# espThrottle.net
KiCad netlist of a schematic drawn in EAGLE
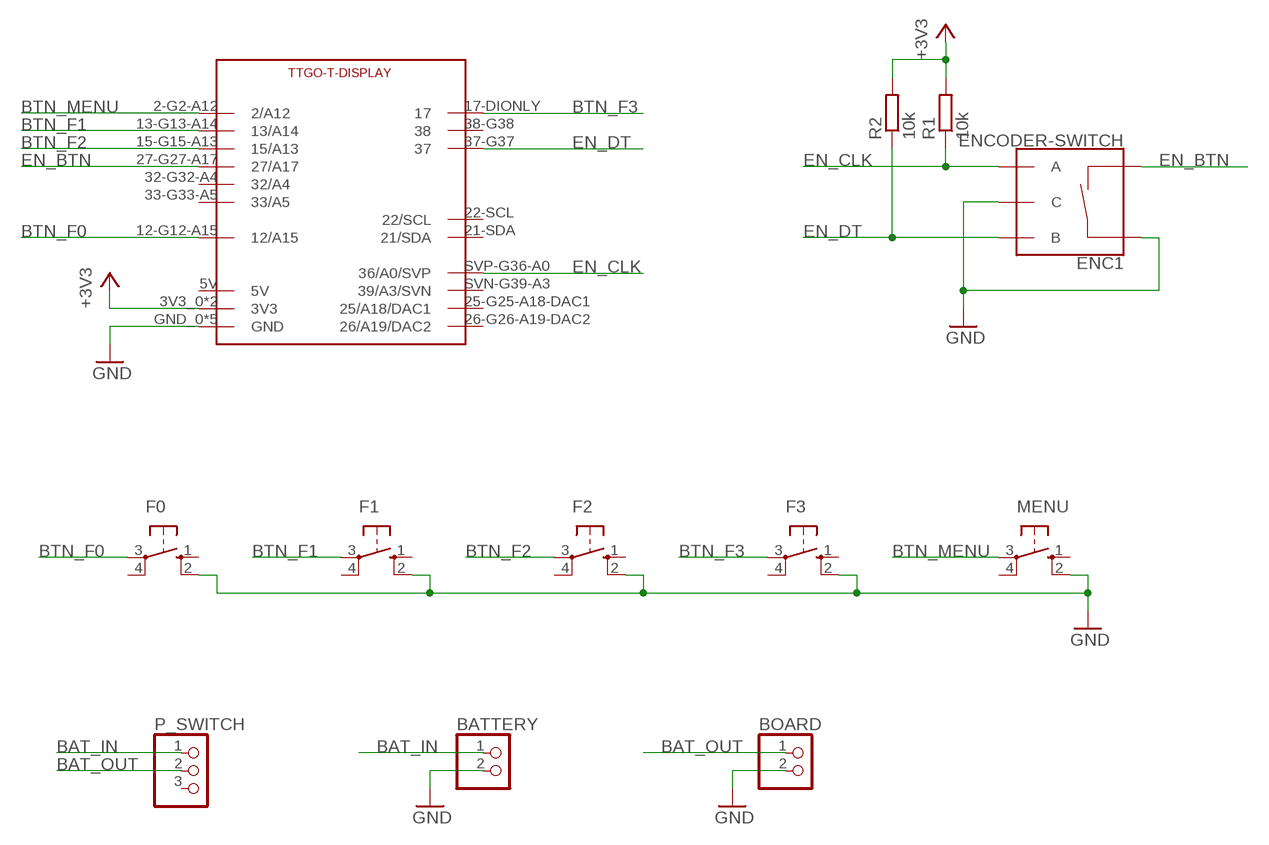
[diagram p0: schematic, sheet 1]

(export (version "E")
  (design (tool "Eeschema 10.0.6"))
  (components
    (comp (ref "BATTERY")
      (value "PINHD-1X2")
      (footprint "eagle-import:1X02")
      (libsource (lib "eagle-import") (part "PINHD-1X2"))
    )
    (comp (ref "BOARD")
      (value "PINHD-1X2")
      (footprint "eagle-import:1X02")
      (libsource (lib "eagle-import") (part "PINHD-1X2"))
    )
    (comp (ref "ENC1")
      (value "ENCODER-SWITCH")
      (footprint "eagle-import:ROTARY_ENC_PLAIN")
      (libsource (lib "eagle-import") (part "ENCODER-SWITCH"))
    )
    (comp (ref "F0")
      (value "10-XX")
      (footprint "eagle-import:B3F-10XX")
      (fields (field (name "MPN") "B3F-1000"))
      (libsource (lib "eagle-import") (part "10-XX"))
    )
    (comp (ref "F1")
      (value "10-XX")
      (footprint "eagle-import:B3F-10XX")
      (fields (field (name "MPN") "B3F-1000"))
      (libsource (lib "eagle-import") (part "10-XX"))
    )
    (comp (ref "F2")
      (value "10-XX")
      (footprint "eagle-import:B3F-10XX")
      (fields (field (name "MPN") "B3F-1000"))
      (libsource (lib "eagle-import") (part "10-XX"))
    )
    (comp (ref "F3")
      (value "10-XX")
      (footprint "eagle-import:B3F-10XX")
      (fields (field (name "MPN") "B3F-1000"))
      (libsource (lib "eagle-import") (part "10-XX"))
    )
    (comp (ref "MENU")
      (value "10-XX")
      (footprint "eagle-import:B3F-10XX")
      (fields (field (name "MPN") "B3F-1000"))
      (libsource (lib "eagle-import") (part "10-XX"))
    )
    (comp (ref "P_SWITCH")
      (value "PINHD-1X3")
      (footprint "eagle-import:1X03")
      (libsource (lib "eagle-import") (part "PINHD-1X3"))
    )
    (comp (ref "R1")
      (value "10k")
      (footprint "eagle-import:0207_12")
      (libsource (lib "eagle-import") (part "R-EU_0207/12"))
    )
    (comp (ref "R2")
      (value "10k")
      (footprint "eagle-import:0207_12")
      (libsource (lib "eagle-import") (part "R-EU_0207/12"))
    )
    (comp (ref "U$1")
      (value "TTGO-T-DISPLAYFRAME")
      (footprint "eagle-import:TTGO-T-DISPLAY-OL")
      (libsource (lib "eagle-import") (part "TTGO-T-DISPLAYFRAME"))
    )
  )
  (nets
    (net (code "1") (name "+3V3") (class "Default")
      (node (ref "R1") (pin "2") (pinfunction "2_2") (pintype "passive"))
      (node (ref "R2") (pin "2") (pinfunction "2_2") (pintype "passive"))
      (node (ref "U$1") (pin "3V3_0") (pinfunction "3V3_3V3_0") (pintype "power_in"))
      (node (ref "U$1") (pin "3V3_1") (pinfunction "3V3_3V3_1") (pintype "power_in"))
    )
    (net (code "2") (name "/5V") (class "Default")
      (node (ref "U$1") (pin "5V") (pinfunction "5V_5V") (pintype "power_in"))
    )
    (net (code "3") (name "/BAT_IN") (class "Default")
      (node (ref "BATTERY") (pin "1") (pinfunction "1_1") (pintype "passive"))
      (node (ref "P_SWITCH") (pin "1") (pinfunction "1_1") (pintype "passive"))
    )
    (net (code "4") (name "/BAT_OUT") (class "Default")
      (node (ref "BOARD") (pin "1") (pinfunction "1_1") (pintype "passive"))
      (node (ref "P_SWITCH") (pin "2") (pinfunction "2_2") (pintype "passive"))
    )
    (net (code "5") (name "/BTN_F0") (class "Default")
      (node (ref "F0") (pin "3") (pinfunction "P_3") (pintype "passive"))
      (node (ref "U$1") (pin "12-G12-A15") (pinfunction "12/A15_12-G12-A15") (pintype "output"))
    )
    (net (code "6") (name "/BTN_F1") (class "Default")
      (node (ref "F1") (pin "3") (pinfunction "P_3") (pintype "passive"))
      (node (ref "U$1") (pin "13-G13-A14") (pinfunction "13/A14_13-G13-A14") (pintype "bidirectional"))
    )
    (net (code "7") (name "/BTN_F2") (class "Default")
      (node (ref "F2") (pin "3") (pinfunction "P_3") (pintype "passive"))
      (node (ref "U$1") (pin "15-G15-A13") (pinfunction "15/A13_15-G15-A13") (pintype "bidirectional"))
    )
    (net (code "8") (name "/BTN_F3") (class "Default")
      (node (ref "F3") (pin "3") (pinfunction "P_3") (pintype "passive"))
      (node (ref "U$1") (pin "17-DIONLY") (pinfunction "17_17-DIONLY") (pintype "bidirectional"))
    )
    (net (code "9") (name "/BTN_MENU") (class "Default")
      (node (ref "MENU") (pin "3") (pinfunction "P_3") (pintype "passive"))
      (node (ref "U$1") (pin "2-G2-A12") (pinfunction "2/A12_2-G2-A12") (pintype "bidirectional"))
    )
    (net (code "10") (name "/EN_BTN") (class "Default")
      (node (ref "ENC1") (pin "SW-") (pinfunction "SW-_SW-") (pintype "bidirectional"))
      (node (ref "U$1") (pin "27-G27-A17") (pinfunction "27/A17_27-G27-A17") (pintype "bidirectional"))
    )
    (net (code "11") (name "/EN_CLK") (class "Default")
      (node (ref "ENC1") (pin "A") (pinfunction "A_A") (pintype "bidirectional"))
      (node (ref "R1") (pin "1") (pinfunction "1_1") (pintype "passive"))
      (node (ref "U$1") (pin "SVP-G36-A0") (pinfunction "36/A0/SVP_SVP-G36-A0") (pintype "bidirectional"))
    )
    (net (code "12") (name "/EN_DT") (class "Default")
      (node (ref "ENC1") (pin "B") (pinfunction "B_B") (pintype "bidirectional"))
      (node (ref "R2") (pin "1") (pinfunction "1_1") (pintype "passive"))
      (node (ref "U$1") (pin "37-G37") (pinfunction "37_37-G37") (pintype "bidirectional"))
    )
    (net (code "13") (name "GND") (class "Default")
      (node (ref "BATTERY") (pin "2") (pinfunction "2_2") (pintype "passive"))
      (node (ref "BOARD") (pin "2") (pinfunction "2_2") (pintype "passive"))
      (node (ref "ENC1") (pin "C") (pinfunction "C_C") (pintype "bidirectional"))
      (node (ref "ENC1") (pin "SW+") (pinfunction "SW+_SW+") (pintype "bidirectional"))
      (node (ref "F0") (pin "2") (pinfunction "S1_2") (pintype "passive"))
      (node (ref "F1") (pin "2") (pinfunction "S1_2") (pintype "passive"))
      (node (ref "F2") (pin "2") (pinfunction "S1_2") (pintype "passive"))
      (node (ref "F3") (pin "2") (pinfunction "S1_2") (pintype "passive"))
      (node (ref "MENU") (pin "2") (pinfunction "S1_2") (pintype "passive"))
      (node (ref "U$1") (pin "GND_0") (pinfunction "GND_GND_0") (pintype "power_in"))
      (node (ref "U$1") (pin "GND_1") (pinfunction "GND_GND_1") (pintype "power_in"))
      (node (ref "U$1") (pin "GND_2") (pinfunction "GND_GND_2") (pintype "power_in"))
      (node (ref "U$1") (pin "GND_3") (pinfunction "GND_GND_3") (pintype "power_in"))
      (node (ref "U$1") (pin "GND_4") (pinfunction "GND_GND_4") (pintype "power_in"))
    )
    (net (code "14") (name "unconnected-(F0-P1-Pad4)") (class "Default")
      (node (ref "F0") (pin "4") (pinfunction "P1_4") (pintype "passive"))
    )
    (net (code "15") (name "unconnected-(F0-S-Pad1)") (class "Default")
      (node (ref "F0") (pin "1") (pinfunction "S_1") (pintype "passive"))
    )
    (net (code "16") (name "unconnected-(F1-P1-Pad4)") (class "Default")
      (node (ref "F1") (pin "4") (pinfunction "P1_4") (pintype "passive"))
    )
    (net (code "17") (name "unconnected-(F1-S-Pad1)") (class "Default")
      (node (ref "F1") (pin "1") (pinfunction "S_1") (pintype "passive"))
    )
    (net (code "18") (name "unconnected-(F2-P1-Pad4)") (class "Default")
      (node (ref "F2") (pin "4") (pinfunction "P1_4") (pintype "passive"))
    )
    (net (code "19") (name "unconnected-(F2-S-Pad1)") (class "Default")
      (node (ref "F2") (pin "1") (pinfunction "S_1") (pintype "passive"))
    )
    (net (code "20") (name "unconnected-(F3-P1-Pad4)") (class "Default")
      (node (ref "F3") (pin "4") (pinfunction "P1_4") (pintype "passive"))
    )
    (net (code "21") (name "unconnected-(F3-S-Pad1)") (class "Default")
      (node (ref "F3") (pin "1") (pinfunction "S_1") (pintype "passive"))
    )
    (net (code "22") (name "unconnected-(MENU-P1-Pad4)") (class "Default")
      (node (ref "MENU") (pin "4") (pinfunction "P1_4") (pintype "passive"))
    )
    (net (code "23") (name "unconnected-(MENU-S-Pad1)") (class "Default")
      (node (ref "MENU") (pin "1") (pinfunction "S_1") (pintype "passive"))
    )
    (net (code "24") (name "unconnected-(P_SWITCH-Pad3)") (class "Default")
      (node (ref "P_SWITCH") (pin "3") (pinfunction "3_3") (pintype "passive"))
    )
    (net (code "25") (name "unconnected-(U$1-21{slash}SDA-Pad21-SDA)") (class "Default")
      (node (ref "U$1") (pin "21-SDA") (pinfunction "21/SDA_21-SDA") (pintype "bidirectional"))
    )
    (net (code "26") (name "unconnected-(U$1-22{slash}SCL-Pad22-SCL)") (class "Default")
      (node (ref "U$1") (pin "22-SCL") (pinfunction "22/SCL_22-SCL") (pintype "bidirectional"))
    )
    (net (code "27") (name "unconnected-(U$1-25{slash}A18{slash}DAC1-Pad25-G25-A18-DAC1)") (class "Default")
      (node (ref "U$1") (pin "25-G25-A18-DAC1") (pinfunction "25/A18/DAC1_25-G25-A18-DAC1") (pintype "bidirectional"))
    )
    (net (code "28") (name "unconnected-(U$1-26{slash}A19{slash}DAC2-Pad26-G26-A19-DAC2)") (class "Default")
      (node (ref "U$1") (pin "26-G26-A19-DAC2") (pinfunction "26/A19/DAC2_26-G26-A19-DAC2") (pintype "bidirectional"))
    )
    (net (code "29") (name "unconnected-(U$1-32{slash}A4-Pad32-G32-A4)") (class "Default")
      (node (ref "U$1") (pin "32-G32-A4") (pinfunction "32/A4_32-G32-A4") (pintype "bidirectional"))
    )
    (net (code "30") (name "unconnected-(U$1-33{slash}A5-Pad33-G33-A5)") (class "Default")
      (node (ref "U$1") (pin "33-G33-A5") (pinfunction "33/A5_33-G33-A5") (pintype "bidirectional"))
    )
    (net (code "31") (name "unconnected-(U$1-38-Pad38-G38)") (class "Default")
      (node (ref "U$1") (pin "38-G38") (pinfunction "38_38-G38") (pintype "bidirectional"))
    )
    (net (code "32") (name "unconnected-(U$1-39{slash}A3{slash}SVN-PadSVN-G39-A3)") (class "Default")
      (node (ref "U$1") (pin "SVN-G39-A3") (pinfunction "39/A3/SVN_SVN-G39-A3") (pintype "bidirectional"))
    )
  )
)
